# AC_zadnja.net
KiCad netlist of a schematic drawn in EAGLE
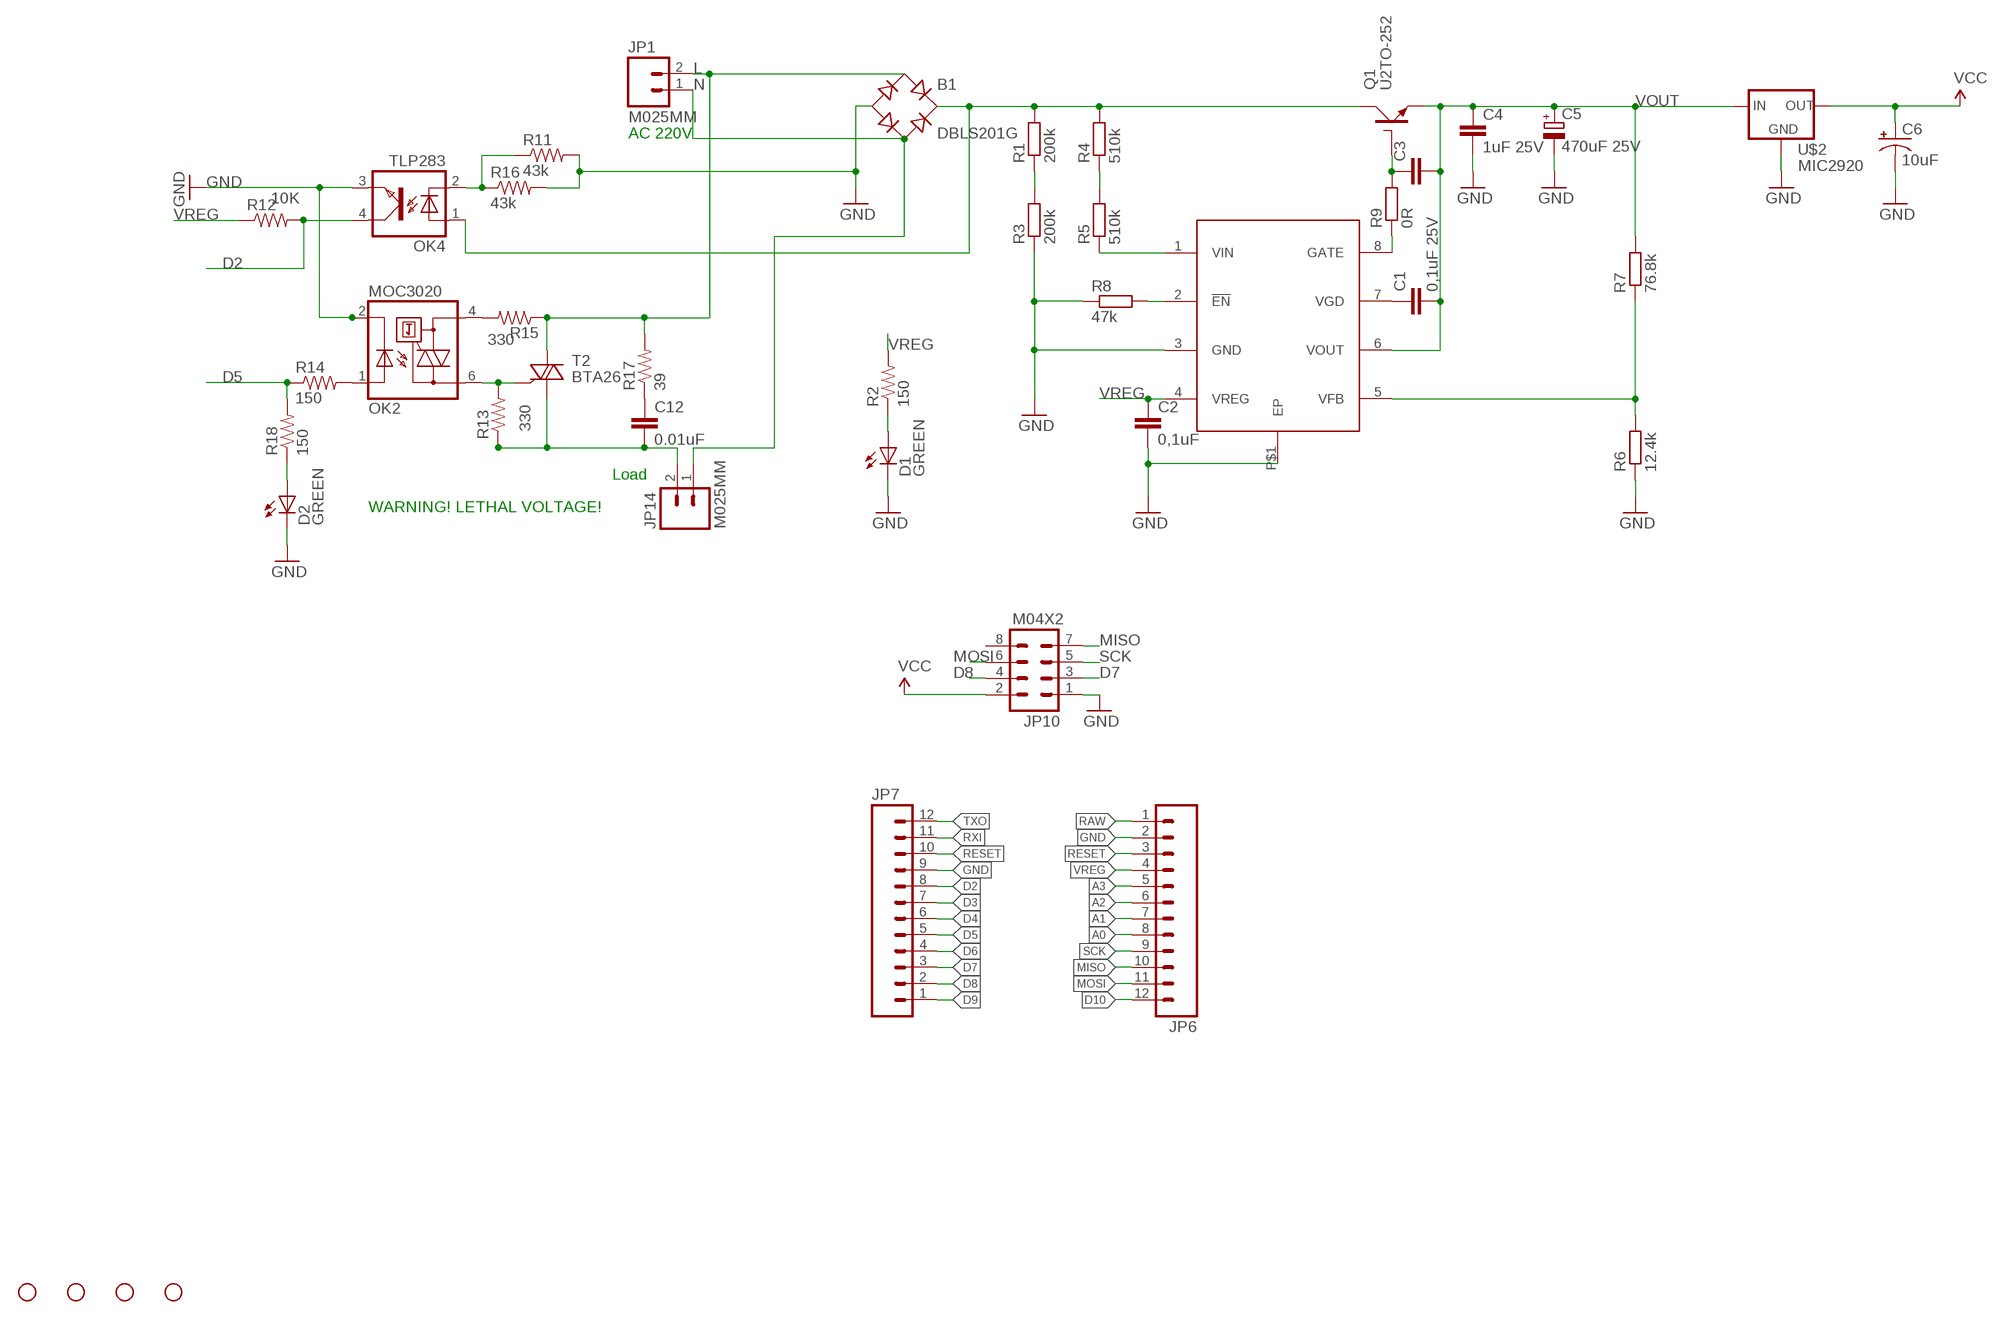
[diagram p0: schematic, sheet 1]

(export (version "E")
  (design (tool "Eeschema 10.0.6"))
  (components
    (comp (ref "B1")
      (value "DBLS201G")
      (footprint "eagle-import:DBS")
      (libsource (lib "eagle-import") (part "DB?GLS201"))
    )
    (comp (ref "C1")
      (value "0,1uF 25V")
      (footprint "eagle-import:C0805")
      (libsource (lib "eagle-import") (part "resistor_C-EUC0805"))
    )
    (comp (ref "C2")
      (value "0,1uF")
      (footprint "eagle-import:C0805")
      (libsource (lib "eagle-import") (part "resistor_C-EUC0805"))
    )
    (comp (ref "C3")
      (value "C-EUC0805")
      (footprint "eagle-import:C0805")
      (libsource (lib "eagle-import") (part "resistor_C-EUC0805"))
    )
    (comp (ref "C4")
      (value "1uF 25V")
      (footprint "eagle-import:C1206")
      (libsource (lib "eagle-import") (part "resistor_C-EUC1206"))
    )
    (comp (ref "C5")
      (value "470uF 25V")
      (footprint "eagle-import:153CLV-1010")
      (libsource (lib "eagle-import") (part "CPOL-EU153CLV-1010"))
    )
    (comp (ref "C6")
      (value "10uF")
      (footprint "eagle-import:EIA3216")
      (libsource (lib "eagle-import") (part "10UF-TANT"))
    )
    (comp (ref "C12")
      (value "0.01uF")
      (footprint "eagle-import:C1206")
      (libsource (lib "eagle-import") (part "C-EUC1206"))
    )
    (comp (ref "D1")
      (value "GREEN")
      (footprint "eagle-import:PLCC2")
      (libsource (lib "eagle-import") (part "_T679-?-1E1F1LG"))
    )
    (comp (ref "D2")
      (value "GREEN")
      (footprint "eagle-import:PLCC2")
      (libsource (lib "eagle-import") (part "_T679-?-1E1F1LG"))
    )
    (comp (ref "JP1")
      (value "M025MM")
      (footprint "eagle-import:SCREWTERMINAL-5MM-2")
      (libsource (lib "eagle-import") (part "M025MM"))
    )
    (comp (ref "JP6")
      (value "M12PTH")
      (footprint "eagle-import:1X12")
      (libsource (lib "eagle-import") (part "M12PTH"))
    )
    (comp (ref "JP7")
      (value "M12PTH")
      (footprint "eagle-import:1X12")
      (libsource (lib "eagle-import") (part "M12PTH"))
    )
    (comp (ref "JP10")
      (value "M04X2")
      (footprint "eagle-import:2X4")
      (libsource (lib "eagle-import") (part "M04X2"))
    )
    (comp (ref "JP14")
      (value "M025MM")
      (footprint "eagle-import:SCREWTERMINAL-5MM-2")
      (libsource (lib "eagle-import") (part "M025MM"))
    )
    (comp (ref "OK2")
      (value "MOC3020")
      (footprint "eagle-import:DIL6-SMD")
      (fields (field (name "MF") "FAIRCHILD SEMICONDUCTOR") (field (name "MPN") "MOC3031SM"))
      (libsource (lib "eagle-import") (part "MOC30S31"))
    )
    (comp (ref "OK4")
      (value "TLP283")
      (footprint "eagle-import:MINI-FLAT-4")
      (libsource (lib "eagle-import") (part "TLP283"))
    )
    (comp (ref "Q1")
      (value "U2TO-252")
      (footprint "eagle-import:D-PAK_TO252AA")
      (libsource (lib "eagle-import") (part "U2TO-252"))
    )
    (comp (ref "R1")
      (value "200k")
      (footprint "eagle-import:M1206")
      (libsource (lib "eagle-import") (part "R-EU_M1206"))
    )
    (comp (ref "R2")
      (value "150")
      (footprint "eagle-import:0805")
      (fields (field (name "OHM") "330"))
      (libsource (lib "eagle-import") (part "RESISTOR0805-RES"))
    )
    (comp (ref "R3")
      (value "200k")
      (footprint "eagle-import:M1206")
      (libsource (lib "eagle-import") (part "R-EU_M1206"))
    )
    (comp (ref "R4")
      (value "510k")
      (footprint "eagle-import:M1206")
      (libsource (lib "eagle-import") (part "R-EU_M1206"))
    )
    (comp (ref "R5")
      (value "510k")
      (footprint "eagle-import:M1206")
      (libsource (lib "eagle-import") (part "R-EU_M1206"))
    )
    (comp (ref "R6")
      (value "12.4k")
      (footprint "eagle-import:M0805")
      (libsource (lib "eagle-import") (part "R-EU_M0805"))
    )
    (comp (ref "R7")
      (value "76.8k")
      (footprint "eagle-import:M0805")
      (libsource (lib "eagle-import") (part "R-EU_M0805"))
    )
    (comp (ref "R8")
      (value "47k")
      (footprint "eagle-import:M0805")
      (libsource (lib "eagle-import") (part "R-EU_M0805"))
    )
    (comp (ref "R9")
      (value "0R")
      (footprint "eagle-import:M0805")
      (libsource (lib "eagle-import") (part "R-EU_M0805"))
    )
    (comp (ref "R11")
      (value "43k")
      (footprint "eagle-import:1206")
      (fields (field (name "K") "45K"))
      (libsource (lib "eagle-import") (part "RESISTOR1206"))
    )
    (comp (ref "R12")
      (value "RESISTOR0805-RES")
      (footprint "eagle-import:0805")
      (fields (field (name "OHM") "10K"))
      (libsource (lib "eagle-import") (part "RESISTOR0805-RES"))
    )
    (comp (ref "R13")
      (value "RESISTOR1206")
      (footprint "eagle-import:1206")
      (fields (field (name "OHM") "330"))
      (libsource (lib "eagle-import") (part "RESISTOR1206"))
    )
    (comp (ref "R14")
      (value "150")
      (footprint "eagle-import:0805")
      (fields (field (name "OHM") "330"))
      (libsource (lib "eagle-import") (part "RESISTOR0805-RES"))
    )
    (comp (ref "R15")
      (value "RESISTOR1206")
      (footprint "eagle-import:1206")
      (fields (field (name "OHM") "330"))
      (libsource (lib "eagle-import") (part "RESISTOR1206"))
    )
    (comp (ref "R16")
      (value "43k")
      (footprint "eagle-import:1206")
      (fields (field (name "K") "45K"))
      (libsource (lib "eagle-import") (part "RESISTOR1206"))
    )
    (comp (ref "R17")
      (value "39")
      (footprint "eagle-import:1206")
      (fields (field (name "K") "45K"))
      (libsource (lib "eagle-import") (part "RESISTOR1206"))
    )
    (comp (ref "R18")
      (value "150")
      (footprint "eagle-import:0805")
      (fields (field (name "OHM") "330"))
      (libsource (lib "eagle-import") (part "RESISTOR0805-RES"))
    )
    (comp (ref "STANDOFF1")
      (value "STAND-OFFTIGHT")
      (footprint "eagle-import:STAND-OFF-TIGHT")
      (libsource (lib "eagle-import") (part "STAND-OFFTIGHT"))
    )
    (comp (ref "STANDOFF2")
      (value "STAND-OFFTIGHT")
      (footprint "eagle-import:STAND-OFF-TIGHT")
      (libsource (lib "eagle-import") (part "STAND-OFFTIGHT"))
    )
    (comp (ref "STANDOFF3")
      (value "STAND-OFFTIGHT")
      (footprint "eagle-import:STAND-OFF-TIGHT")
      (libsource (lib "eagle-import") (part "STAND-OFFTIGHT"))
    )
    (comp (ref "STANDOFF4")
      (value "STAND-OFFTIGHT")
      (footprint "eagle-import:STAND-OFF-TIGHT")
      (libsource (lib "eagle-import") (part "STAND-OFFTIGHT"))
    )
    (comp (ref "T2")
      (value "BTA26")
      (footprint "eagle-import:DPACK_2")
      (libsource (lib "eagle-import") (part "BTA26D2PAK"))
    )
    (comp (ref "U$1")
      (value "U1")
      (footprint "eagle-import:SOIC08")
      (libsource (lib "eagle-import") (part "U1"))
    )
    (comp (ref "U$2")
      (value "MIC2920")
      (footprint "eagle-import:SOT223")
      (libsource (lib "eagle-import") (part "V_REG_MIC2920"))
    )
  )
  (nets
    (net (code "1") (name "/L") (class "Default")
      (node (ref "B1") (pin "AC1") (pinfunction "AC1_AC1") (pintype "passive"))
      (node (ref "JP1") (pin "2") (pinfunction "2_2") (pintype "passive"))
      (node (ref "R15") (pin "1") (pinfunction "1_1") (pintype "passive"))
      (node (ref "R17") (pin "2") (pinfunction "2_2") (pintype "passive"))
      (node (ref "T2") (pin "D") (pinfunction "A2_D") (pintype "passive"))
    )
    (net (code "2") (name "/N") (class "Default")
      (node (ref "B1") (pin "AC2") (pinfunction "AC2_AC2") (pintype "passive"))
      (node (ref "JP1") (pin "1") (pinfunction "1_1") (pintype "passive"))
      (node (ref "JP14") (pin "1") (pinfunction "1_1") (pintype "passive"))
    )
    (net (code "3") (name "/VOUT") (class "Default")
      (node (ref "C1") (pin "2") (pinfunction "2_2") (pintype "passive"))
      (node (ref "C3") (pin "2") (pinfunction "2_2") (pintype "passive"))
      (node (ref "C4") (pin "1") (pinfunction "1_1") (pintype "passive"))
      (node (ref "C5") (pin "+") (pinfunction "+_+") (pintype "passive"))
      (node (ref "Q1") (pin "3") (pinfunction "E_3") (pintype "passive"))
      (node (ref "R7") (pin "2") (pinfunction "2_2") (pintype "passive"))
      (node (ref "U$1") (pin "6") (pinfunction "VOUT_6") (pintype "bidirectional"))
      (node (ref "U$2") (pin "1") (pinfunction "IN_1") (pintype "input"))
    )
    (net (code "4") (name "A0") (class "Default")
      (node (ref "JP6") (pin "8") (pinfunction "8_8") (pintype "passive"))
    )
    (net (code "5") (name "A1") (class "Default")
      (node (ref "JP6") (pin "7") (pinfunction "7_7") (pintype "passive"))
    )
    (net (code "6") (name "A2") (class "Default")
      (node (ref "JP6") (pin "6") (pinfunction "6_6") (pintype "passive"))
    )
    (net (code "7") (name "A3") (class "Default")
      (node (ref "JP6") (pin "5") (pinfunction "5_5") (pintype "passive"))
    )
    (net (code "8") (name "D2") (class "Default")
      (node (ref "JP7") (pin "8") (pinfunction "8_8") (pintype "passive"))
      (node (ref "OK4") (pin "4") (pinfunction "COL_4") (pintype "passive"))
      (node (ref "R12") (pin "2") (pinfunction "2_2") (pintype "passive"))
    )
    (net (code "9") (name "D3") (class "Default")
      (node (ref "JP7") (pin "7") (pinfunction "7_7") (pintype "passive"))
    )
    (net (code "10") (name "D4") (class "Default")
      (node (ref "JP7") (pin "6") (pinfunction "6_6") (pintype "passive"))
    )
    (net (code "11") (name "D5") (class "Default")
      (node (ref "JP7") (pin "5") (pinfunction "5_5") (pintype "passive"))
      (node (ref "R14") (pin "1") (pinfunction "1_1") (pintype "passive"))
      (node (ref "R18") (pin "2") (pinfunction "2_2") (pintype "passive"))
    )
    (net (code "12") (name "D6") (class "Default")
      (node (ref "JP7") (pin "4") (pinfunction "4_4") (pintype "passive"))
    )
    (net (code "13") (name "D7") (class "Default")
      (node (ref "JP10") (pin "3") (pinfunction "3_3") (pintype "passive"))
      (node (ref "JP7") (pin "3") (pinfunction "3_3") (pintype "passive"))
    )
    (net (code "14") (name "D8") (class "Default")
      (node (ref "JP10") (pin "4") (pinfunction "4_4") (pintype "passive"))
      (node (ref "JP7") (pin "2") (pinfunction "2_2") (pintype "passive"))
    )
    (net (code "15") (name "D9") (class "Default")
      (node (ref "JP7") (pin "1") (pinfunction "1_1") (pintype "passive"))
    )
    (net (code "16") (name "D10") (class "Default")
      (node (ref "JP6") (pin "12") (pinfunction "12_12") (pintype "passive"))
    )
    (net (code "17") (name "GND") (class "Default")
      (node (ref "B1") (pin "-") (pinfunction "-_-") (pintype "passive"))
      (node (ref "C2") (pin "2") (pinfunction "2_2") (pintype "passive"))
      (node (ref "C4") (pin "2") (pinfunction "2_2") (pintype "passive"))
      (node (ref "C5") (pin "-") (pinfunction "-_-") (pintype "passive"))
      (node (ref "C6") (pin "C") (pinfunction "-_C") (pintype "passive"))
      (node (ref "D1") (pin "C") (pinfunction "C_C") (pintype "passive"))
      (node (ref "D2") (pin "C") (pinfunction "C_C") (pintype "passive"))
      (node (ref "JP10") (pin "1") (pinfunction "1_1") (pintype "passive"))
      (node (ref "JP6") (pin "2") (pinfunction "2_2") (pintype "passive"))
      (node (ref "JP7") (pin "9") (pinfunction "9_9") (pintype "passive"))
      (node (ref "OK2") (pin "2") (pinfunction "C_2") (pintype "passive"))
      (node (ref "OK4") (pin "3") (pinfunction "EMIT_3") (pintype "passive"))
      (node (ref "R11") (pin "2") (pinfunction "2_2") (pintype "passive"))
      (node (ref "R16") (pin "2") (pinfunction "2_2") (pintype "passive"))
      (node (ref "R3") (pin "1") (pinfunction "1_1") (pintype "passive"))
      (node (ref "R6") (pin "1") (pinfunction "1_1") (pintype "passive"))
      (node (ref "R8") (pin "1") (pinfunction "1_1") (pintype "passive"))
      (node (ref "U$1") (pin "3") (pinfunction "GND_3") (pintype "bidirectional"))
      (node (ref "U$1") (pin "P$1") (pinfunction "EP_P$1") (pintype "bidirectional"))
      (node (ref "U$2") (pin "2") (pinfunction "GND_2") (pintype "input"))
    )
    (net (code "18") (name "MISO") (class "Default")
      (node (ref "JP10") (pin "7") (pinfunction "7_7") (pintype "passive"))
      (node (ref "JP6") (pin "10") (pinfunction "10_10") (pintype "passive"))
    )
    (net (code "19") (name "MOSI") (class "Default")
      (node (ref "JP10") (pin "6") (pinfunction "6_6") (pintype "passive"))
      (node (ref "JP6") (pin "11") (pinfunction "11_11") (pintype "passive"))
    )
    (net (code "20") (name "Net-(C12-Pad1)") (class "Default")
      (node (ref "C12") (pin "1") (pinfunction "1_1") (pintype "passive"))
      (node (ref "R17") (pin "1") (pinfunction "1_1") (pintype "passive"))
    )
    (net (code "21") (name "Net-(D1-PadA)") (class "Default")
      (node (ref "D1") (pin "A") (pinfunction "A_A") (pintype "passive"))
      (node (ref "R2") (pin "1") (pinfunction "1_1") (pintype "passive"))
    )
    (net (code "22") (name "Net-(D2-PadA)") (class "Default")
      (node (ref "D2") (pin "A") (pinfunction "A_A") (pintype "passive"))
      (node (ref "R18") (pin "1") (pinfunction "1_1") (pintype "passive"))
    )
    (net (code "23") (name "Net-(OK2-A)") (class "Default")
      (node (ref "OK2") (pin "1") (pinfunction "A_1") (pintype "passive"))
      (node (ref "R14") (pin "2") (pinfunction "2_2") (pintype "passive"))
    )
    (net (code "24") (name "Net-(OK2-A1)") (class "Default")
      (node (ref "OK2") (pin "4") (pinfunction "A1_4") (pintype "passive"))
      (node (ref "R15") (pin "2") (pinfunction "2_2") (pintype "passive"))
    )
    (net (code "25") (name "Net-(OK2-A2)") (class "Default")
      (node (ref "OK2") (pin "6") (pinfunction "A2_6") (pintype "passive"))
      (node (ref "R13") (pin "2") (pinfunction "2_2") (pintype "passive"))
      (node (ref "T2") (pin "S") (pinfunction "G_S") (pintype "passive"))
    )
    (net (code "26") (name "Net-(OK4-A)") (class "Default")
      (node (ref "B1") (pin "+") (pinfunction "+_+") (pintype "passive"))
      (node (ref "OK4") (pin "1") (pinfunction "A_1") (pintype "passive"))
      (node (ref "Q1") (pin "4") (pinfunction "C_4") (pintype "passive"))
      (node (ref "R1") (pin "2") (pinfunction "2_2") (pintype "passive"))
      (node (ref "R4") (pin "2") (pinfunction "2_2") (pintype "passive"))
    )
    (net (code "27") (name "Net-(OK4-C)") (class "Default")
      (node (ref "OK4") (pin "2") (pinfunction "C_2") (pintype "passive"))
      (node (ref "R11") (pin "1") (pinfunction "1_1") (pintype "passive"))
      (node (ref "R16") (pin "1") (pinfunction "1_1") (pintype "passive"))
    )
    (net (code "28") (name "Net-(Q1-G)") (class "Default")
      (node (ref "C3") (pin "1") (pinfunction "1_1") (pintype "passive"))
      (node (ref "Q1") (pin "1") (pinfunction "G_1") (pintype "passive"))
      (node (ref "R9") (pin "2") (pinfunction "2_2") (pintype "passive"))
    )
    (net (code "29") (name "Net-(R1-Pad1)") (class "Default")
      (node (ref "R1") (pin "1") (pinfunction "1_1") (pintype "passive"))
      (node (ref "R3") (pin "2") (pinfunction "2_2") (pintype "passive"))
    )
    (net (code "30") (name "Net-(R4-Pad1)") (class "Default")
      (node (ref "R4") (pin "1") (pinfunction "1_1") (pintype "passive"))
      (node (ref "R5") (pin "2") (pinfunction "2_2") (pintype "passive"))
    )
    (net (code "31") (name "Net-(T2-A1)") (class "Default")
      (node (ref "C12") (pin "2") (pinfunction "2_2") (pintype "passive"))
      (node (ref "JP14") (pin "2") (pinfunction "2_2") (pintype "passive"))
      (node (ref "R13") (pin "1") (pinfunction "1_1") (pintype "passive"))
      (node (ref "T2") (pin "G") (pinfunction "A1_G") (pintype "passive"))
    )
    (net (code "32") (name "Net-(U$1-GATE)") (class "Default")
      (node (ref "R9") (pin "1") (pinfunction "1_1") (pintype "passive"))
      (node (ref "U$1") (pin "8") (pinfunction "GATE_8") (pintype "bidirectional"))
    )
    (net (code "33") (name "Net-(U$1-VFB)") (class "Default")
      (node (ref "R6") (pin "2") (pinfunction "2_2") (pintype "passive"))
      (node (ref "R7") (pin "1") (pinfunction "1_1") (pintype "passive"))
      (node (ref "U$1") (pin "5") (pinfunction "VFB_5") (pintype "bidirectional"))
    )
    (net (code "34") (name "Net-(U$1-VGD)") (class "Default")
      (node (ref "C1") (pin "1") (pinfunction "1_1") (pintype "passive"))
      (node (ref "U$1") (pin "7") (pinfunction "VGD_7") (pintype "bidirectional"))
    )
    (net (code "35") (name "Net-(U$1-VIN)") (class "Default")
      (node (ref "R5") (pin "1") (pinfunction "1_1") (pintype "passive"))
      (node (ref "U$1") (pin "1") (pinfunction "VIN_1") (pintype "bidirectional"))
    )
    (net (code "36") (name "Net-(U$1-~{EN})") (class "Default")
      (node (ref "R8") (pin "2") (pinfunction "2_2") (pintype "passive"))
      (node (ref "U$1") (pin "2") (pinfunction "~{EN}_2") (pintype "bidirectional"))
    )
    (net (code "37") (name "RAW") (class "Default")
      (node (ref "JP6") (pin "1") (pinfunction "1_1") (pintype "passive"))
    )
    (net (code "38") (name "RESET") (class "Default")
      (node (ref "JP6") (pin "3") (pinfunction "3_3") (pintype "passive"))
      (node (ref "JP7") (pin "10") (pinfunction "10_10") (pintype "passive"))
    )
    (net (code "39") (name "RXI") (class "Default")
      (node (ref "JP7") (pin "11") (pinfunction "11_11") (pintype "passive"))
    )
    (net (code "40") (name "SCK") (class "Default")
      (node (ref "JP10") (pin "5") (pinfunction "5_5") (pintype "passive"))
      (node (ref "JP6") (pin "9") (pinfunction "9_9") (pintype "passive"))
    )
    (net (code "41") (name "TXO") (class "Default")
      (node (ref "JP7") (pin "12") (pinfunction "12_12") (pintype "passive"))
    )
    (net (code "42") (name "VCC") (class "Default")
      (node (ref "C6") (pin "A") (pinfunction "+_A") (pintype "passive"))
      (node (ref "JP10") (pin "2") (pinfunction "2_2") (pintype "passive"))
      (node (ref "U$2") (pin "3") (pinfunction "OUT_3") (pintype "passive"))
    )
    (net (code "43") (name "VREG") (class "Default")
      (node (ref "C2") (pin "1") (pinfunction "1_1") (pintype "passive"))
      (node (ref "JP6") (pin "4") (pinfunction "4_4") (pintype "passive"))
      (node (ref "R12") (pin "1") (pinfunction "1_1") (pintype "passive"))
      (node (ref "R2") (pin "2") (pinfunction "2_2") (pintype "passive"))
      (node (ref "U$1") (pin "4") (pinfunction "VREG_4") (pintype "bidirectional"))
    )
    (net (code "44") (name "unconnected-(JP10-Pad8)") (class "Default")
      (node (ref "JP10") (pin "8") (pinfunction "8_8") (pintype "passive"))
    )
  )
)
